# LiPoChargerBooster5V1A.net
KiCad netlist of a schematic drawn in EAGLE
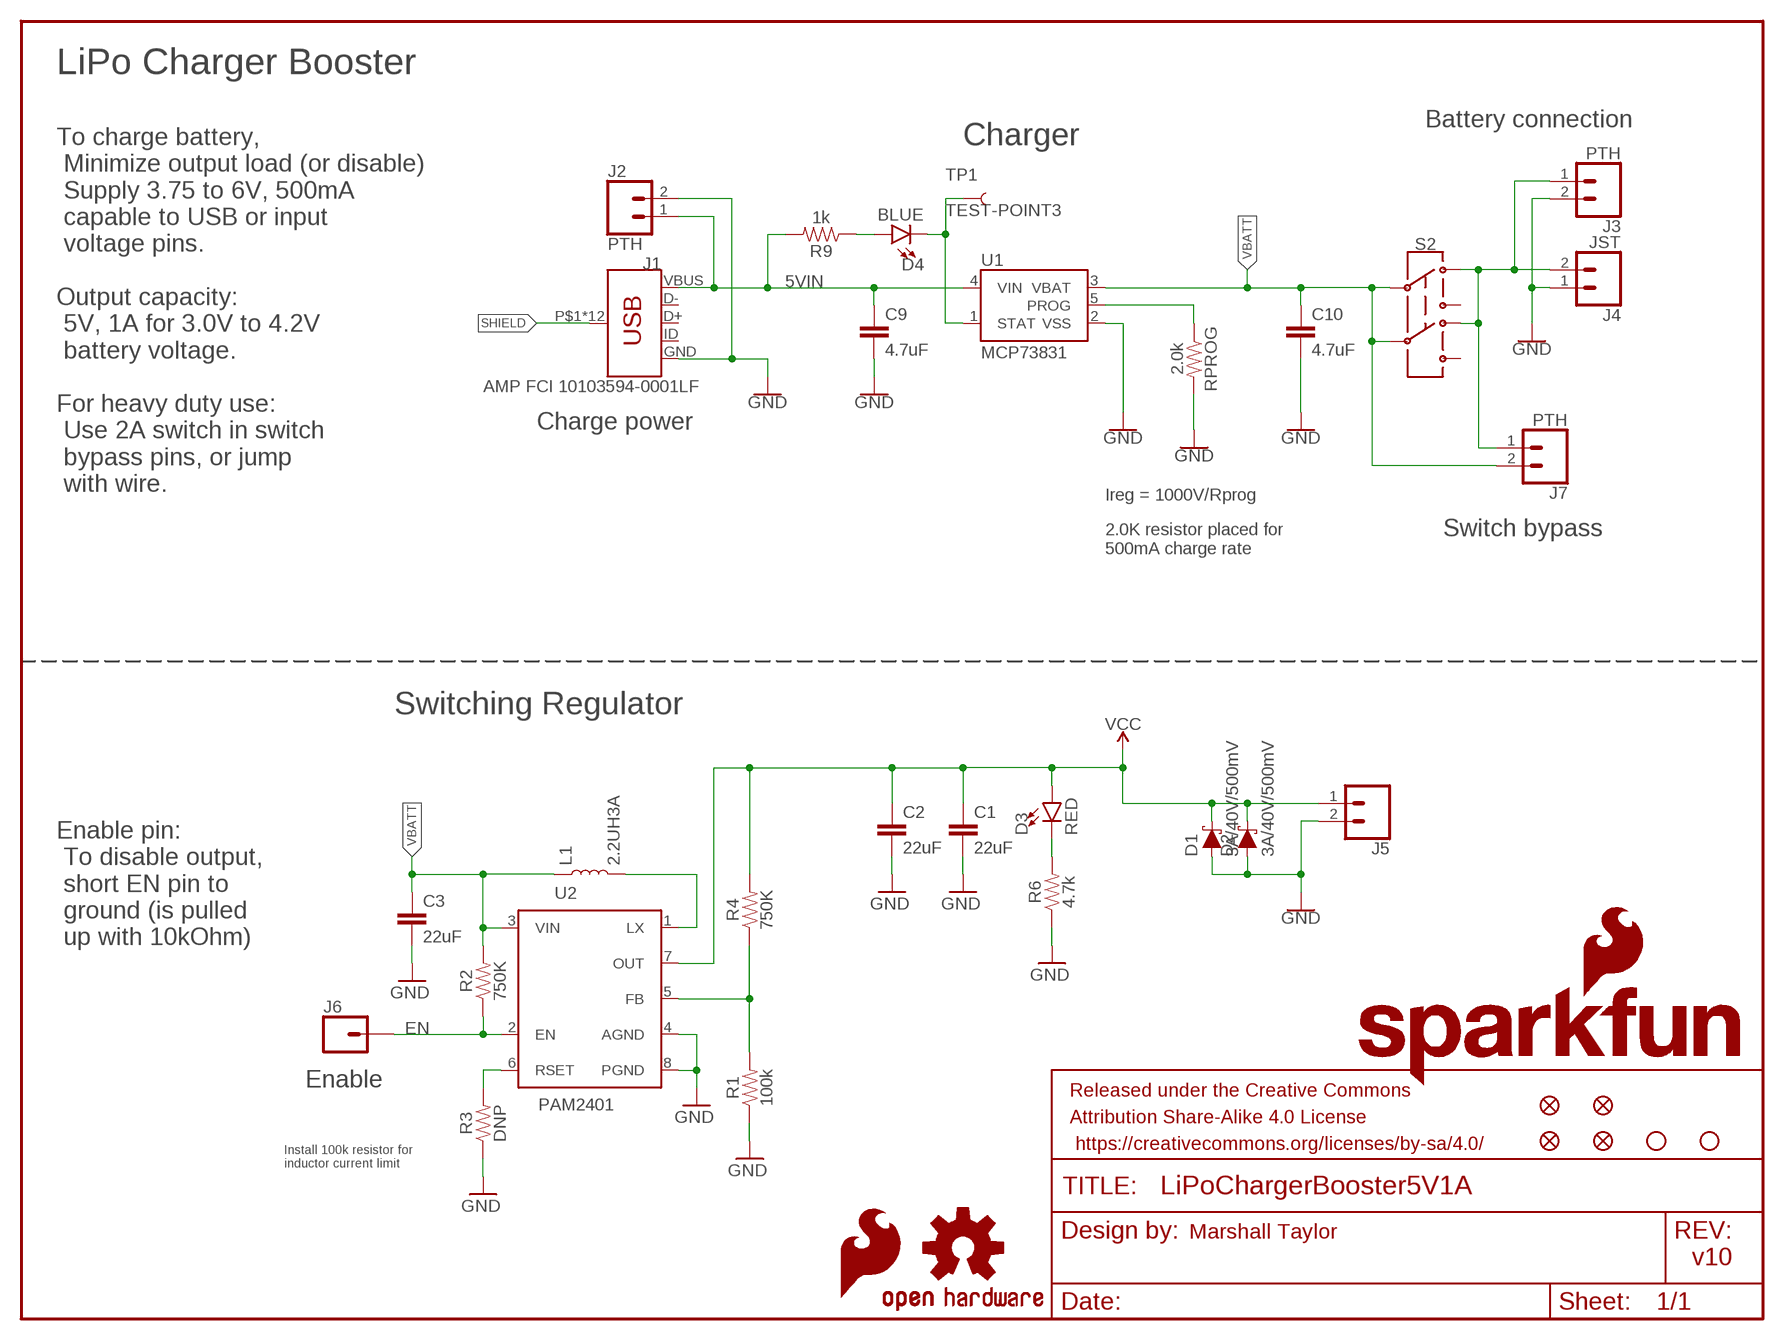
[diagram p0: schematic, sheet 1]

(export (version "E")
  (design (tool "Eeschema 10.0.6"))
  (components
    (comp (ref "C1")
      (value "22uF")
      (footprint "eagle-import:0805")
      (libsource (lib "eagle-import") (part "22UF-0805-6.3V-20%"))
    )
    (comp (ref "C2")
      (value "22uF")
      (footprint "eagle-import:0805")
      (libsource (lib "eagle-import") (part "22UF-0805-6.3V-20%"))
    )
    (comp (ref "C3")
      (value "22uF")
      (footprint "eagle-import:0805")
      (libsource (lib "eagle-import") (part "22UF-0805-6.3V-20%"))
    )
    (comp (ref "C9")
      (value "4.7uF")
      (footprint "eagle-import:0603")
      (libsource (lib "eagle-import") (part "4.7UF0603"))
    )
    (comp (ref "C10")
      (value "4.7uF")
      (footprint "eagle-import:0603")
      (libsource (lib "eagle-import") (part "4.7UF0603"))
    )
    (comp (ref "D1")
      (value "3A/40V/500mV")
      (footprint "eagle-import:SMA-DIODE")
      (libsource (lib "eagle-import") (part "DIODE-SCHOTTKY-B340A"))
    )
    (comp (ref "D2")
      (value "3A/40V/500mV")
      (footprint "eagle-import:SMA-DIODE")
      (libsource (lib "eagle-import") (part "DIODE-SCHOTTKY-B340A"))
    )
    (comp (ref "D3")
      (value "RED")
      (footprint "eagle-import:LED-0603")
      (libsource (lib "eagle-import") (part "LED-RED0603"))
    )
    (comp (ref "D4")
      (value "BLUE")
      (footprint "eagle-import:LED-0603")
      (libsource (lib "eagle-import") (part "LED-BLUE0603"))
    )
    (comp (ref "FRAME1")
      (value "FRAME-LETTER")
      (footprint "eagle-import:CREATIVE_COMMONS")
      (libsource (lib "eagle-import") (part "FRAME-LETTER"))
    )
    (comp (ref "J1")
      (value "AMP FCI 10103594-0001LF")
      (footprint "eagle-import:USB-MICROB-PTH")
      (libsource (lib "eagle-import") (part "USB_MICRO-B_HALF_PTH"))
    )
    (comp (ref "J2")
      (value "PTH")
      (footprint "eagle-import:1X02")
      (libsource (lib "eagle-import") (part "CONN_02"))
    )
    (comp (ref "J3")
      (value "PTH")
      (footprint "eagle-import:1X02")
      (libsource (lib "eagle-import") (part "CONN_02"))
    )
    (comp (ref "J4")
      (value "JST")
      (footprint "eagle-import:JST-2-SMD")
      (libsource (lib "eagle-import") (part "CONN_02-JST-2MM-SMT"))
    )
    (comp (ref "J5")
      (value "CONN_02")
      (footprint "eagle-import:1X02")
      (libsource (lib "eagle-import") (part "CONN_02"))
    )
    (comp (ref "J6")
      (value "CONN_01")
      (footprint "eagle-import:1X01")
      (libsource (lib "eagle-import") (part "CONN_01"))
    )
    (comp (ref "J7")
      (value "PTH")
      (footprint "eagle-import:1X02")
      (libsource (lib "eagle-import") (part "CONN_02"))
    )
    (comp (ref "JP1")
      (value "FIDUCIAL1X2")
      (footprint "eagle-import:FIDUCIAL-1X2")
      (libsource (lib "eagle-import") (part "FIDUCIAL1X2"))
    )
    (comp (ref "JP2")
      (value "FIDUCIAL1X2")
      (footprint "eagle-import:FIDUCIAL-1X2")
      (libsource (lib "eagle-import") (part "FIDUCIAL1X2"))
    )
    (comp (ref "JP3")
      (value "SFE_LOGO_NAME_FLAME.1_INCH")
      (footprint "eagle-import:SFE_LOGO_NAME_FLAME_.1")
      (libsource (lib "eagle-import") (part "SFE_LOGO_NAME_FLAME.1_INCH"))
    )
    (comp (ref "JP4")
      (value "FIDUCIAL1X2")
      (footprint "eagle-import:FIDUCIAL-1X2")
      (libsource (lib "eagle-import") (part "FIDUCIAL1X2"))
    )
    (comp (ref "JP6")
      (value "STAND-OFF")
      (footprint "eagle-import:STAND-OFF")
      (libsource (lib "eagle-import") (part "STAND-OFF"))
    )
    (comp (ref "JP7")
      (value "STAND-OFF")
      (footprint "eagle-import:STAND-OFF")
      (libsource (lib "eagle-import") (part "STAND-OFF"))
    )
    (comp (ref "JP16")
      (value "FIDUCIAL1X2")
      (footprint "eagle-import:FIDUCIAL-1X2")
      (libsource (lib "eagle-import") (part "FIDUCIAL1X2"))
    )
    (comp (ref "L1")
      (value "2.2UH3A")
      (footprint "eagle-import:INDUCTOR_4X4MM")
      (libsource (lib "eagle-import") (part "INDUCTOR-IFSC1515AHER2R2M01"))
    )
    (comp (ref "LOGO1")
      (value "SFE_LOGO_FLAME.1_INCH")
      (footprint "eagle-import:SFE_LOGO_FLAME_.1")
      (libsource (lib "eagle-import") (part "SFE_LOGO_FLAME.1_INCH"))
    )
    (comp (ref "R1")
      (value "100k")
      (footprint "eagle-import:0603")
      (libsource (lib "eagle-import") (part "100KOHM-0603-1/10W-1%"))
    )
    (comp (ref "R2")
      (value "750K")
      (footprint "eagle-import:0603")
      (libsource (lib "eagle-import") (part "750KOHM-0603-1/10W-1%"))
    )
    (comp (ref "R3")
      (value "DNP")
      (footprint "eagle-import:0603")
      (libsource (lib "eagle-import") (part "100KOHM-0603-1/10W-1%"))
    )
    (comp (ref "R4")
      (value "750K")
      (footprint "eagle-import:0603")
      (libsource (lib "eagle-import") (part "750KOHM-0603-1/10W-1%"))
    )
    (comp (ref "R6")
      (value "4.7k")
      (footprint "eagle-import:0603")
      (libsource (lib "eagle-import") (part "4.7KOHM-0603-1/10W-1%"))
    )
    (comp (ref "R9")
      (value "1k")
      (footprint "eagle-import:0603")
      (libsource (lib "eagle-import") (part "1KOHM-0603-1/10W-1%"))
    )
    (comp (ref "RPROG")
      (value "2.0k")
      (footprint "eagle-import:0603")
      (libsource (lib "eagle-import") (part "2.0KOHM-0603-1/10W-5%"))
    )
    (comp (ref "S2")
      (value "SWITCH-DPDT-SMD-AYZ0202")
      (footprint "eagle-import:SWITCH_DPDT_SMD_AYZ0202")
      (libsource (lib "eagle-import") (part "SWITCH-DPDT-SMD-AYZ0202"))
    )
    (comp (ref "TP1")
      (value "TEST-POINT3")
      (footprint "eagle-import:PAD.03X.03")
      (libsource (lib "eagle-import") (part "TEST-POINT3"))
    )
    (comp (ref "U$1")
      (value "OSHW-LOGOS")
      (footprint "eagle-import:OSHW-LOGO-S")
      (libsource (lib "eagle-import") (part "OSHW-LOGOS"))
    )
    (comp (ref "U1")
      (value "MCP73831")
      (footprint "eagle-import:SOT23-5")
      (libsource (lib "eagle-import") (part "MCP73831"))
    )
    (comp (ref "U2")
      (value "PAM2401")
      (footprint "eagle-import:MSOP8")
      (libsource (lib "eagle-import") (part "PAM2401"))
    )
  )
  (nets
    (net (code "1") (name "/5VIN") (class "Default")
      (node (ref "C9") (pin "1") (pinfunction "1_1") (pintype "passive"))
      (node (ref "J1") (pin "VBUS") (pinfunction "VBUS_VBUS") (pintype "power_in"))
      (node (ref "J2") (pin "1") (pinfunction "1_1") (pintype "passive"))
      (node (ref "R9") (pin "2") (pinfunction "2_2") (pintype "passive"))
      (node (ref "U1") (pin "4") (pinfunction "VIN_4") (pintype "power_in"))
    )
    (net (code "2") (name "/EN") (class "Default")
      (node (ref "J6") (pin "1") (pinfunction "1_1") (pintype "passive"))
      (node (ref "R2") (pin "1") (pinfunction "1_1") (pintype "passive"))
      (node (ref "U2") (pin "2") (pinfunction "EN_2") (pintype "bidirectional"))
    )
    (net (code "3") (name "GND") (class "Default")
      (node (ref "C1") (pin "2") (pinfunction "2_2") (pintype "passive"))
      (node (ref "C10") (pin "2") (pinfunction "2_2") (pintype "passive"))
      (node (ref "C2") (pin "2") (pinfunction "2_2") (pintype "passive"))
      (node (ref "C3") (pin "2") (pinfunction "2_2") (pintype "passive"))
      (node (ref "C9") (pin "2") (pinfunction "2_2") (pintype "passive"))
      (node (ref "D1") (pin "A") (pinfunction "A_A") (pintype "passive"))
      (node (ref "D2") (pin "A") (pinfunction "A_A") (pintype "passive"))
      (node (ref "J1") (pin "GND") (pinfunction "GND_GND") (pintype "power_in"))
      (node (ref "J2") (pin "2") (pinfunction "2_2") (pintype "passive"))
      (node (ref "J3") (pin "2") (pinfunction "2_2") (pintype "passive"))
      (node (ref "J4") (pin "1") (pinfunction "2_1") (pintype "passive"))
      (node (ref "J5") (pin "2") (pinfunction "2_2") (pintype "passive"))
      (node (ref "R1") (pin "1") (pinfunction "1_1") (pintype "passive"))
      (node (ref "R3") (pin "1") (pinfunction "1_1") (pintype "passive"))
      (node (ref "R6") (pin "1") (pinfunction "1_1") (pintype "passive"))
      (node (ref "RPROG") (pin "2") (pinfunction "2_2") (pintype "passive"))
      (node (ref "U1") (pin "2") (pinfunction "VSS_2") (pintype "power_in"))
      (node (ref "U2") (pin "4") (pinfunction "AGND_4") (pintype "bidirectional"))
      (node (ref "U2") (pin "8") (pinfunction "PGND_8") (pintype "bidirectional"))
    )
    (net (code "4") (name "Net-(D3-PadC)") (class "Default")
      (node (ref "D3") (pin "C") (pinfunction "C_C") (pintype "passive"))
      (node (ref "R6") (pin "2") (pinfunction "2_2") (pintype "passive"))
    )
    (net (code "5") (name "Net-(D4-PadA)") (class "Default")
      (node (ref "D4") (pin "A") (pinfunction "A_A") (pintype "passive"))
      (node (ref "R9") (pin "1") (pinfunction "1_1") (pintype "passive"))
    )
    (net (code "6") (name "Net-(J4-1)") (class "Default")
      (node (ref "J3") (pin "1") (pinfunction "1_1") (pintype "passive"))
      (node (ref "J4") (pin "2") (pinfunction "1_2") (pintype "passive"))
      (node (ref "J7") (pin "1") (pinfunction "1_1") (pintype "passive"))
      (node (ref "S2") (pin "1") (pinfunction "1_1") (pintype "bidirectional"))
      (node (ref "S2") (pin "4") (pinfunction "4_4") (pintype "bidirectional"))
    )
    (net (code "7") (name "Net-(L1-2)") (class "Default")
      (node (ref "L1") (pin "P$2") (pinfunction "2_P$2") (pintype "passive"))
      (node (ref "U2") (pin "1") (pinfunction "LX_1") (pintype "bidirectional"))
    )
    (net (code "8") (name "Net-(TP1-1)") (class "Default")
      (node (ref "D4") (pin "C") (pinfunction "C_C") (pintype "passive"))
      (node (ref "TP1") (pin "P$1") (pinfunction "1_P$1") (pintype "bidirectional"))
      (node (ref "U1") (pin "1") (pinfunction "STAT_1") (pintype "output"))
    )
    (net (code "9") (name "Net-(U1-PROG)") (class "Default")
      (node (ref "RPROG") (pin "1") (pinfunction "1_1") (pintype "passive"))
      (node (ref "U1") (pin "5") (pinfunction "PROG_5") (pintype "input"))
    )
    (net (code "10") (name "Net-(U2-FB)") (class "Default")
      (node (ref "R1") (pin "2") (pinfunction "2_2") (pintype "passive"))
      (node (ref "R4") (pin "1") (pinfunction "1_1") (pintype "passive"))
      (node (ref "U2") (pin "5") (pinfunction "FB_5") (pintype "bidirectional"))
    )
    (net (code "11") (name "Net-(U2-RSET)") (class "Default")
      (node (ref "R3") (pin "2") (pinfunction "2_2") (pintype "passive"))
      (node (ref "U2") (pin "6") (pinfunction "RSET_6") (pintype "bidirectional"))
    )
    (net (code "12") (name "SHIELD") (class "Default")
      (node (ref "J1") (pin "P$1") (pinfunction "SHIELD_P$1") (pintype "bidirectional"))
      (node (ref "J1") (pin "P$10") (pinfunction "SHIELD_P$10") (pintype "bidirectional"))
      (node (ref "J1") (pin "P$12") (pinfunction "SHIELD_P$12") (pintype "bidirectional"))
      (node (ref "J1") (pin "P$2") (pinfunction "SHIELD_P$2") (pintype "bidirectional"))
      (node (ref "J1") (pin "P$3") (pinfunction "SHIELD_P$3") (pintype "bidirectional"))
      (node (ref "J1") (pin "P$4") (pinfunction "SHIELD_P$4") (pintype "bidirectional"))
      (node (ref "J1") (pin "P$6") (pinfunction "SHIELD_P$6") (pintype "bidirectional"))
      (node (ref "J1") (pin "P$8") (pinfunction "SHIELD_P$8") (pintype "bidirectional"))
      (node (ref "J1") (pin "SHEILD2") (pinfunction "SHIELD_SHEILD2") (pintype "bidirectional"))
      (node (ref "J1") (pin "SHIELD") (pinfunction "SHIELD_SHIELD") (pintype "bidirectional"))
      (node (ref "J1") (pin "SHIELD3") (pinfunction "SHIELD_SHIELD3") (pintype "bidirectional"))
      (node (ref "J1") (pin "SHIELD4") (pinfunction "SHIELD_SHIELD4") (pintype "bidirectional"))
    )
    (net (code "13") (name "VBATT") (class "Default")
      (node (ref "C10") (pin "1") (pinfunction "1_1") (pintype "passive"))
      (node (ref "C3") (pin "1") (pinfunction "1_1") (pintype "passive"))
      (node (ref "J7") (pin "2") (pinfunction "2_2") (pintype "passive"))
      (node (ref "L1") (pin "P$1") (pinfunction "1_P$1") (pintype "passive"))
      (node (ref "R2") (pin "2") (pinfunction "2_2") (pintype "passive"))
      (node (ref "S2") (pin "2") (pinfunction "2_2") (pintype "bidirectional"))
      (node (ref "S2") (pin "5") (pinfunction "5_5") (pintype "bidirectional"))
      (node (ref "U1") (pin "3") (pinfunction "VBAT_3") (pintype "power_in"))
      (node (ref "U2") (pin "3") (pinfunction "VIN_3") (pintype "bidirectional"))
    )
    (net (code "14") (name "VCC") (class "Default")
      (node (ref "C1") (pin "1") (pinfunction "1_1") (pintype "passive"))
      (node (ref "C2") (pin "1") (pinfunction "1_1") (pintype "passive"))
      (node (ref "D1") (pin "C") (pinfunction "C_C") (pintype "passive"))
      (node (ref "D2") (pin "C") (pinfunction "C_C") (pintype "passive"))
      (node (ref "D3") (pin "A") (pinfunction "A_A") (pintype "passive"))
      (node (ref "J5") (pin "1") (pinfunction "1_1") (pintype "passive"))
      (node (ref "R4") (pin "2") (pinfunction "2_2") (pintype "passive"))
      (node (ref "U2") (pin "7") (pinfunction "OUT_7") (pintype "bidirectional"))
    )
    (net (code "15") (name "unconnected-(J1-PadD+)") (class "Default")
      (node (ref "J1") (pin "D+") (pinfunction "D+_D+") (pintype "bidirectional"))
    )
    (net (code "16") (name "unconnected-(J1-PadD-)") (class "Default")
      (node (ref "J1") (pin "D-") (pinfunction "D-_D-") (pintype "bidirectional"))
    )
    (net (code "17") (name "unconnected-(J1-PadID)") (class "Default")
      (node (ref "J1") (pin "ID") (pinfunction "ID_ID") (pintype "bidirectional"))
    )
    (net (code "18") (name "unconnected-(S2-Pad3)") (class "Default")
      (node (ref "S2") (pin "3") (pinfunction "3_3") (pintype "bidirectional"))
    )
    (net (code "19") (name "unconnected-(S2-Pad6)") (class "Default")
      (node (ref "S2") (pin "6") (pinfunction "6_6") (pintype "bidirectional"))
    )
  )
)
